# TESTSensorBoard.net
KiCad netlist of a schematic drawn in Altium Designer
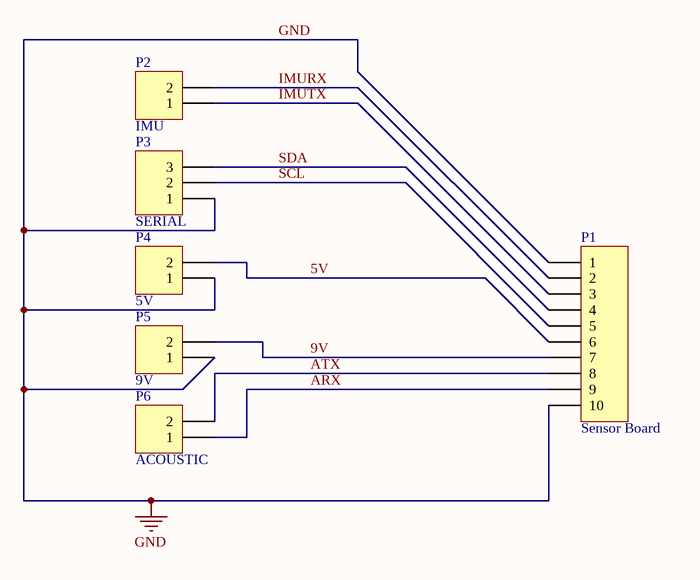
[diagram p0: TESTSensorBoard.SchDoc]

(export (version "E")
  (design (tool "Eeschema 10.0.6"))
  (components
    (comp (ref "P1")
      (value "Sensor Board")
      (footprint "ICV 2,5/10-G-5,08")
      (description "Header, 10-Pin")
      (libsource (lib "Pheonix Contact") (part "ICV 2,5/10-G-5,08"))
    )
    (comp (ref "P2")
      (value "IMU")
      (footprint "HDR1X2")
      (description "Header, 2-Pin")
      (fields (field (name "PUBLISHER") "Altium Limited"))
      (libsource (lib "Miscellaneous Connectors") (part "Header 2"))
    )
    (comp (ref "P3")
      (value "SERIAL")
      (footprint "HDR1X3")
      (description "Header, 3-Pin")
      (fields (field (name "PUBLISHER") "Altium Limited"))
      (libsource (lib "Miscellaneous Connectors") (part "Header 3"))
    )
    (comp (ref "P4")
      (value "5V")
      (footprint "HDR1X2")
      (description "Header, 2-Pin")
      (fields (field (name "PUBLISHER") "Altium Limited"))
      (libsource (lib "Miscellaneous Connectors") (part "Header 2"))
    )
    (comp (ref "P5")
      (value "9V")
      (footprint "HDR1X2")
      (description "Header, 2-Pin")
      (fields (field (name "PUBLISHER") "Altium Limited"))
      (libsource (lib "Miscellaneous Connectors") (part "Header 2"))
    )
    (comp (ref "P6")
      (value "ACOUSTIC")
      (footprint "HDR1X2")
      (description "Header, 2-Pin")
      (fields (field (name "PUBLISHER") "Altium Limited"))
      (libsource (lib "Miscellaneous Connectors") (part "Header 2"))
    )
  )
  (nets
    (net (code "1") (name "/5V") (class "Default")
      (node (ref "P1") (pin "6") (pinfunction "6_6") (pintype "passive"))
      (node (ref "P4") (pin "2") (pinfunction "2_2") (pintype "passive"))
    )
    (net (code "2") (name "/9V") (class "Default")
      (node (ref "P1") (pin "7") (pinfunction "7_7") (pintype "passive"))
      (node (ref "P5") (pin "2") (pinfunction "2_2") (pintype "passive"))
    )
    (net (code "3") (name "/ARX") (class "Default")
      (node (ref "P1") (pin "9") (pinfunction "9_9") (pintype "passive"))
      (node (ref "P6") (pin "1") (pinfunction "1_1") (pintype "passive"))
    )
    (net (code "4") (name "/ATX") (class "Default")
      (node (ref "P1") (pin "8") (pinfunction "8_8") (pintype "passive"))
      (node (ref "P6") (pin "2") (pinfunction "2_2") (pintype "passive"))
    )
    (net (code "5") (name "/IMURX") (class "Default")
      (node (ref "P1") (pin "2") (pinfunction "2_2") (pintype "passive"))
      (node (ref "P2") (pin "2") (pinfunction "2_2") (pintype "passive"))
    )
    (net (code "6") (name "/IMUTX") (class "Default")
      (node (ref "P1") (pin "3") (pinfunction "3_3") (pintype "passive"))
      (node (ref "P2") (pin "1") (pinfunction "1_1") (pintype "passive"))
    )
    (net (code "7") (name "/SCL") (class "Default")
      (node (ref "P1") (pin "5") (pinfunction "5_5") (pintype "passive"))
      (node (ref "P3") (pin "2") (pinfunction "2_2") (pintype "passive"))
    )
    (net (code "8") (name "/SDA") (class "Default")
      (node (ref "P1") (pin "4") (pinfunction "4_4") (pintype "passive"))
      (node (ref "P3") (pin "3") (pinfunction "3_3") (pintype "passive"))
    )
    (net (code "9") (name "GND") (class "Default")
      (node (ref "P1") (pin "1") (pinfunction "1_1") (pintype "passive"))
      (node (ref "P1") (pin "10") (pinfunction "10_10") (pintype "passive"))
      (node (ref "P3") (pin "1") (pinfunction "1_1") (pintype "passive"))
      (node (ref "P4") (pin "1") (pinfunction "1_1") (pintype "passive"))
      (node (ref "P5") (pin "1") (pinfunction "1_1") (pintype "passive"))
    )
  )
)
